# 1-Schematic_ESP32_Wroom_mini.net
KiCad netlist of a schematic drawn in EasyEDA
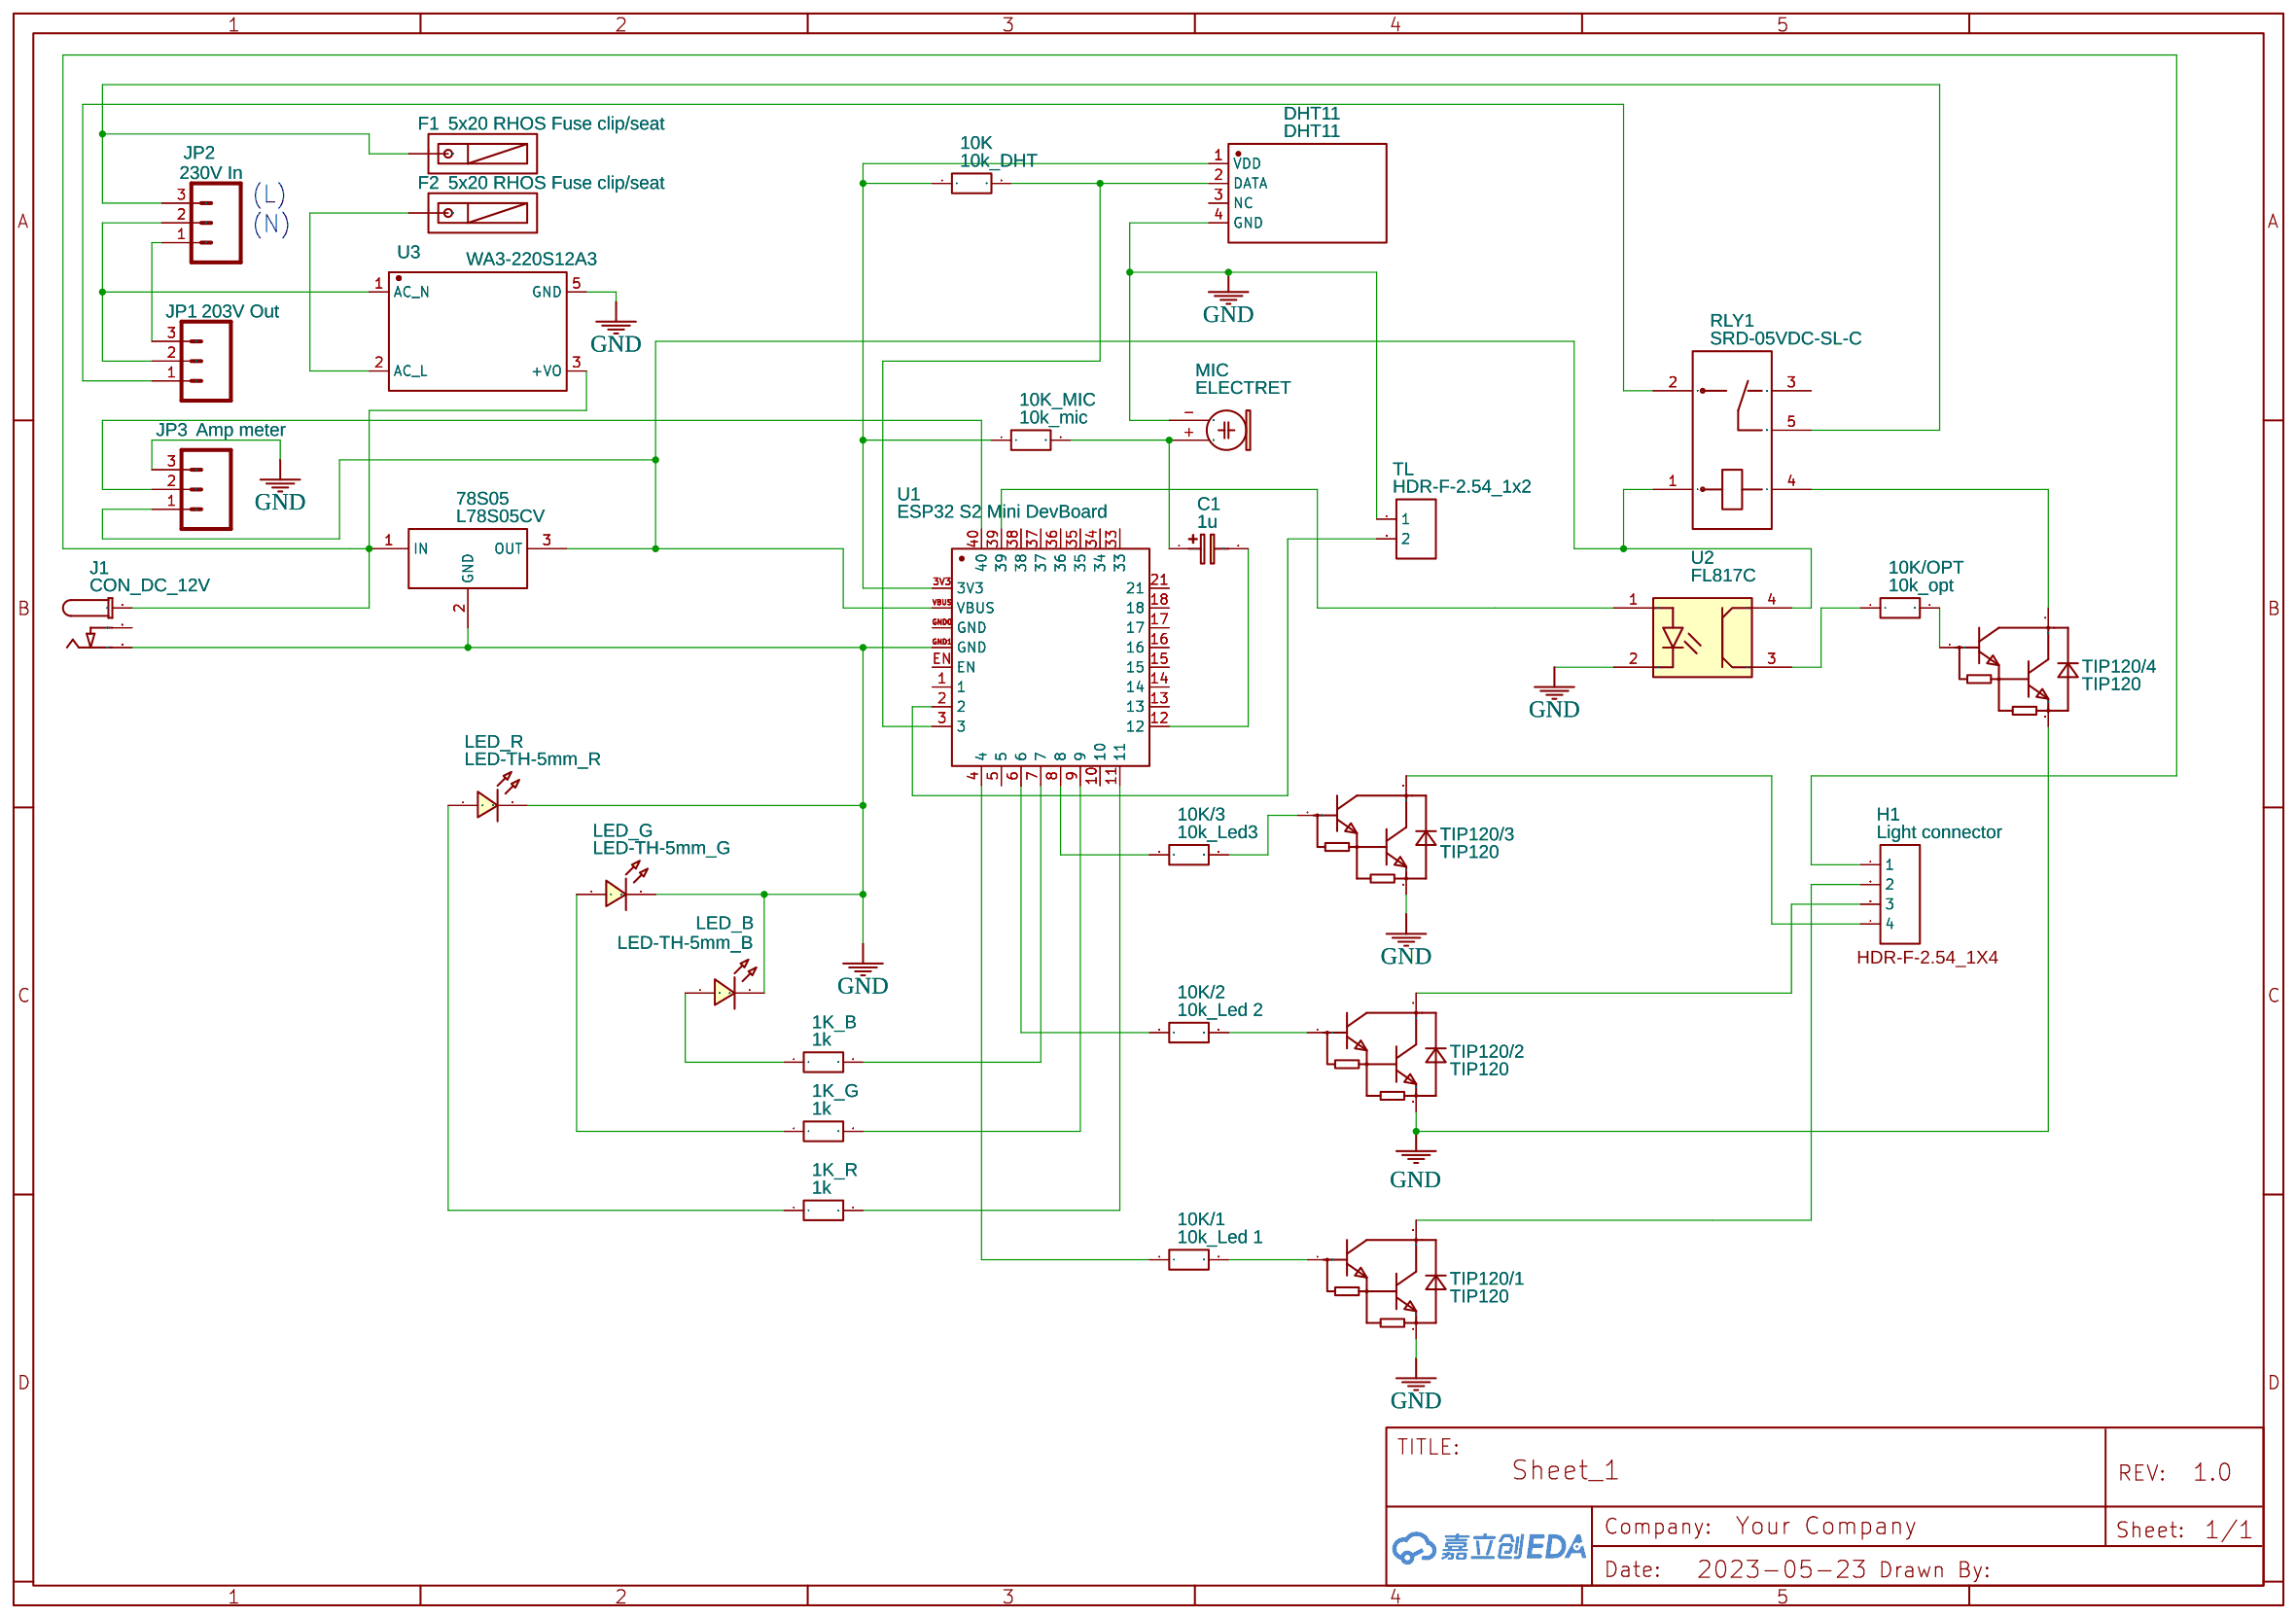
[diagram p0: schematic sheet]

(export (version "E")
  (design (tool "Eeschema 10.0.6"))
  (components
    (comp (ref "1K_B") (value "1k") (libsource (lib "") (part "R_AXIAL-0.3_EU_1")))
    (comp (ref "1K_G") (value "1k") (libsource (lib "") (part "R_AXIAL-0.3_EU")))
    (comp (ref "1K_R") (value "1k") (libsource (lib "") (part "R_AXIAL-0.3_EU_2")))
    (comp (ref "10K") (value "10k_DHT") (libsource (lib "") (part "R_AXIAL-0.4_EU_3")))
    (comp (ref "10K/1") (value "10k_Led 1") (libsource (lib "") (part "R_AXIAL-0.4_EU_2")))
    (comp (ref "10K/2") (value "10k_Led 2") (libsource (lib "") (part "R_AXIAL-0.4_EU_2")))
    (comp (ref "10K/3") (value "10k_Led3") (libsource (lib "") (part "R_AXIAL-0.4_EU_2")))
    (comp (ref "10K/OPT") (value "10k_opt") (libsource (lib "") (part "R_AXIAL-0.4_EU")))
    (comp (ref "10K_MIC") (value "10k_mic") (libsource (lib "") (part "R_AXIAL-0.4_EU_1")))
    (comp (ref "78S05")
      (value "L78S05CV")
      (fields (field (name "Manufacturer") "ST(意法半导体)"))
      (libsource (lib "") (part "L78S05CV"))
    )
    (comp (ref "C1") (value "1u") (libsource (lib "") (part "CE_TH_D3.0×F1.5_EU")))
    (comp (ref "DHT11")
      (value "DHT11")
      (fields (field (name "Manufacturer") "广州奥松"))
      (libsource (lib "") (part "DHT11"))
    )
    (comp (ref "F1")
      (value "5x20 RHOS Fuse clip/seat")
      (fields (field (name "Manufacturer Part") "5x20 环保 保险管夹/座") (field (name "Manufacturer") "xcfuse(旭程)"))
      (libsource (lib "") (part "5x20 RHOS Fuse clip/seat"))
    )
    (comp (ref "F2")
      (value "5x20 RHOS Fuse clip/seat")
      (fields (field (name "Manufacturer Part") "5x20 环保 保险管夹/座") (field (name "Manufacturer") "xcfuse(旭程)"))
      (libsource (lib "") (part "5x20 RHOS Fuse clip/seat"))
    )
    (comp (ref "H1") (value "Light connector") (libsource (lib "") (part "HDR-F-2.54_1x4")))
    (comp (ref "J1") (value "CON_DC_12V") (libsource (lib "") (part "CON_DC_M-DC_PTH")))
    (comp (ref "JP1") (value "203V Out") (libsource (lib "") (part "M03")))
    (comp (ref "JP2") (value "230V In") (libsource (lib "") (part "M03")))
    (comp (ref "JP3") (value "Amp meter") (libsource (lib "") (part "M03")))
    (comp (ref "LED_B") (value "LED-TH-5mm_B") (libsource (lib "") (part "LED-TH-5mm_B")))
    (comp (ref "LED_G")
      (value "LED-TH-5mm_G")
      (fields
        (field (name "Manufacturer Part") "333-2SYGD/S530-E2")
        (field (name "Manufacturer") "EVERLIGHT(台湾亿光)")
      )
      (libsource (lib "") (part "LED-TH-5mm_G"))
    )
    (comp (ref "LED_R")
      (value "LED-TH-5mm_R")
      (fields
        (field (name "Manufacturer Part") "333-2SURD/S530-A3")
        (field (name "Manufacturer") "EVERLIGHT(台湾亿光)")
      )
      (libsource (lib "") (part "LED-TH-5mm_R"))
    )
    (comp (ref "MIC") (value "ELECTRET") (libsource (lib "") (part "ELECTRET")))
    (comp (ref "RLY1")
      (value "SRD-05VDC-SL-C")
      (fields (field (name "Manufacturer") "松乐"))
      (libsource (lib "") (part "SRD-05VDC-SL-C"))
    )
    (comp (ref "TIP120/1")
      (value "TIP120")
      (fields (field (name "Manufacturer") "ST(意法半导体)"))
      (libsource (lib "") (part "TIP120"))
    )
    (comp (ref "TIP120/2")
      (value "TIP120")
      (fields (field (name "Manufacturer") "ST(意法半导体)"))
      (libsource (lib "") (part "TIP120"))
    )
    (comp (ref "TIP120/3")
      (value "TIP120")
      (fields (field (name "Manufacturer") "ST(意法半导体)"))
      (libsource (lib "") (part "TIP120"))
    )
    (comp (ref "TIP120/4")
      (value "TIP120")
      (fields (field (name "Manufacturer") "ST(意法半导体)"))
      (libsource (lib "") (part "TIP120"))
    )
    (comp (ref "TL") (value "HDR-F-2.54_1x2") (libsource (lib "") (part "HDR-F-2.54_1x2")))
    (comp (ref "U1") (value "ESP32 S2 Mini DevBoard") (libsource (lib "") (part "ESP32 S2 Mini DevBoard")))
    (comp (ref "U2")
      (value "FL817C")
      (fields (field (name "Manufacturer") "FANGJING"))
      (libsource (lib "") (part "FL817C"))
    )
    (comp (ref "U3")
      (value "WA3-220S12A3")
      (fields (field (name "Manufacturer") "AIPULNION(爱浦电子)"))
      (libsource (lib "") (part "WA3-220S12A3"))
    )
  )
  (nets
    (net (code "1") (name "GND") (class "Default")
      (node (ref "78S05") (pin "2") (pinfunction "GND_2") (pintype "passive"))
      (node (ref "DHT11") (pin "4") (pinfunction "GND_4") (pintype "unspecified"))
      (node (ref "J1") (pin "P3") (pinfunction "P2_P3") (pintype "unspecified"))
      (node (ref "JP3") (pin "3") (pinfunction "3_3") (pintype "unspecified"))
      (node (ref "LED_B") (pin "2") (pinfunction "2_2") (pintype "unspecified"))
      (node (ref "LED_G") (pin "2") (pinfunction "2_2") (pintype "unspecified"))
      (node (ref "LED_R") (pin "2") (pinfunction "2_2") (pintype "unspecified"))
      (node (ref "MIC") (pin "-") (pinfunction "1_-") (pintype "unspecified"))
      (node (ref "TIP120/1") (pin "3") (pinfunction "E_3") (pintype "input"))
      (node (ref "TIP120/2") (pin "3") (pinfunction "E_3") (pintype "input"))
      (node (ref "TIP120/3") (pin "3") (pinfunction "E_3") (pintype "input"))
      (node (ref "TIP120/4") (pin "3") (pinfunction "E_3") (pintype "input"))
      (node (ref "TL") (pin "1") (pinfunction "1_1") (pintype "input"))
      (node (ref "U1") (pin "GND1") (pinfunction "GND_GND1") (pintype "unspecified"))
      (node (ref "U2") (pin "2") (pinfunction "2_2") (pintype "unspecified"))
      (node (ref "U3") (pin "5") (pinfunction "GND_5") (pintype "unspecified"))
    )
    (net (code "2") (name "Net-(1K_B-Pad1)") (class "Default")
      (node (ref "1K_B") (pin "1") (pinfunction "1_1") (pintype "unspecified"))
      (node (ref "LED_B") (pin "1") (pinfunction "1_1") (pintype "unspecified"))
    )
    (net (code "3") (name "Net-(1K_B-Pad2)") (class "Default")
      (node (ref "1K_B") (pin "2") (pinfunction "2_2") (pintype "unspecified"))
      (node (ref "U1") (pin "7") (pinfunction "7_7") (pintype "unspecified"))
    )
    (net (code "4") (name "Net-(1K_G-Pad1)") (class "Default")
      (node (ref "1K_G") (pin "1") (pinfunction "1_1") (pintype "unspecified"))
      (node (ref "LED_G") (pin "1") (pinfunction "1_1") (pintype "unspecified"))
    )
    (net (code "5") (name "Net-(1K_G-Pad2)") (class "Default")
      (node (ref "1K_G") (pin "2") (pinfunction "2_2") (pintype "unspecified"))
      (node (ref "U1") (pin "9") (pinfunction "9_9") (pintype "unspecified"))
    )
    (net (code "6") (name "Net-(1K_R-Pad1)") (class "Default")
      (node (ref "1K_R") (pin "1") (pinfunction "1_1") (pintype "unspecified"))
      (node (ref "LED_R") (pin "1") (pinfunction "1_1") (pintype "unspecified"))
    )
    (net (code "7") (name "Net-(1K_R-Pad2)") (class "Default")
      (node (ref "1K_R") (pin "2") (pinfunction "2_2") (pintype "unspecified"))
      (node (ref "U1") (pin "11") (pinfunction "11_11") (pintype "unspecified"))
    )
    (net (code "8") (name "Net-(10K/1-Pad1)") (class "Default")
      (node (ref "10K/1") (pin "1") (pinfunction "1_1") (pintype "unspecified"))
      (node (ref "U1") (pin "4") (pinfunction "4_4") (pintype "unspecified"))
    )
    (net (code "9") (name "Net-(10K/2-Pad1)") (class "Default")
      (node (ref "10K/2") (pin "1") (pinfunction "1_1") (pintype "unspecified"))
      (node (ref "U1") (pin "6") (pinfunction "6_6") (pintype "unspecified"))
    )
    (net (code "10") (name "Net-(10K/3-Pad1)") (class "Default")
      (node (ref "10K/3") (pin "1") (pinfunction "1_1") (pintype "unspecified"))
      (node (ref "U1") (pin "8") (pinfunction "8_8") (pintype "unspecified"))
    )
    (net (code "11") (name "Net-(10K/OPT-Pad1)") (class "Default")
      (node (ref "10K/OPT") (pin "1") (pinfunction "1_1") (pintype "unspecified"))
      (node (ref "U2") (pin "3") (pinfunction "3_3") (pintype "unspecified"))
    )
    (net (code "12") (name "Net-(78S05-IN)") (class "Default")
      (node (ref "78S05") (pin "1") (pinfunction "IN_1") (pintype "passive"))
      (node (ref "H1") (pin "1") (pinfunction "1_1") (pintype "unspecified"))
      (node (ref "J1") (pin "P1") (pinfunction "P1_P1") (pintype "unspecified"))
      (node (ref "U3") (pin "3") (pinfunction "+VO_3") (pintype "unspecified"))
    )
    (net (code "13") (name "Net-(78S05-OUT)") (class "Default")
      (node (ref "78S05") (pin "3") (pinfunction "OUT_3") (pintype "passive"))
      (node (ref "JP3") (pin "1") (pinfunction "1_1") (pintype "unspecified"))
      (node (ref "RLY1") (pin "1") (pinfunction "1_1") (pintype "input"))
      (node (ref "U1") (pin "VBUS") (pinfunction "VBUS_VBUS") (pintype "unspecified"))
      (node (ref "U2") (pin "4") (pinfunction "4_4") (pintype "unspecified"))
    )
    (net (code "14") (name "Net-(C1-Pad2)") (class "Default")
      (node (ref "C1") (pin "2") (pinfunction "2_2") (pintype "unspecified"))
      (node (ref "U1") (pin "12") (pinfunction "12_12") (pintype "unspecified"))
    )
    (net (code "15") (name "Net-(DHT11-DATA)") (class "Default")
      (node (ref "10K") (pin "2") (pinfunction "2_2") (pintype "unspecified"))
      (node (ref "DHT11") (pin "2") (pinfunction "DATA_2") (pintype "unspecified"))
      (node (ref "U1") (pin "3") (pinfunction "3_3") (pintype "unspecified"))
    )
    (net (code "16") (name "Net-(DHT11-VDD)") (class "Default")
      (node (ref "10K") (pin "1") (pinfunction "1_1") (pintype "unspecified"))
      (node (ref "10K_MIC") (pin "1") (pinfunction "1_1") (pintype "unspecified"))
      (node (ref "DHT11") (pin "1") (pinfunction "VDD_1") (pintype "unspecified"))
      (node (ref "U1") (pin "3V3") (pinfunction "3V3_3V3") (pintype "unspecified"))
    )
    (net (code "17") (name "Net-(F1-Pad1)") (class "Default")
      (node (ref "F1") (pin "1") (pinfunction "1_1") (pintype "unspecified"))
      (node (ref "JP2") (pin "3") (pinfunction "3_3") (pintype "unspecified"))
      (node (ref "RLY1") (pin "5") (pinfunction "5_5") (pintype "input"))
    )
    (net (code "18") (name "Net-(JP1-Pad1)") (class "Default")
      (node (ref "JP1") (pin "1") (pinfunction "1_1") (pintype "unspecified"))
      (node (ref "RLY1") (pin "2") (pinfunction "2_2") (pintype "input"))
    )
    (net (code "19") (name "Net-(JP1-Pad3)") (class "Default")
      (node (ref "JP1") (pin "3") (pinfunction "3_3") (pintype "unspecified"))
      (node (ref "JP2") (pin "1") (pinfunction "1_1") (pintype "unspecified"))
    )
    (net (code "20") (name "Net-(JP3-Pad2)") (class "Default")
      (node (ref "JP3") (pin "2") (pinfunction "2_2") (pintype "unspecified"))
      (node (ref "U1") (pin "40") (pinfunction "40_40") (pintype "unspecified"))
    )
    (net (code "21") (name "Net-(MIC-2)") (class "Default")
      (node (ref "10K_MIC") (pin "2") (pinfunction "2_2") (pintype "unspecified"))
      (node (ref "C1") (pin "1") (pinfunction "1_1") (pintype "unspecified"))
      (node (ref "MIC") (pin "+") (pinfunction "2_+") (pintype "unspecified"))
    )
    (net (code "22") (name "Net-(TIP120/1-B)") (class "Default")
      (node (ref "10K/1") (pin "2") (pinfunction "2_2") (pintype "unspecified"))
      (node (ref "TIP120/1") (pin "1") (pinfunction "B_1") (pintype "input"))
    )
    (net (code "23") (name "Net-(TIP120/1-C)") (class "Default")
      (node (ref "H1") (pin "2") (pinfunction "2_2") (pintype "unspecified"))
      (node (ref "TIP120/1") (pin "2") (pinfunction "C_2") (pintype "input"))
    )
    (net (code "24") (name "Net-(TIP120/2-B)") (class "Default")
      (node (ref "10K/2") (pin "2") (pinfunction "2_2") (pintype "unspecified"))
      (node (ref "TIP120/2") (pin "1") (pinfunction "B_1") (pintype "input"))
    )
    (net (code "25") (name "Net-(TIP120/2-C)") (class "Default")
      (node (ref "H1") (pin "3") (pinfunction "3_3") (pintype "unspecified"))
      (node (ref "TIP120/2") (pin "2") (pinfunction "C_2") (pintype "input"))
    )
    (net (code "26") (name "Net-(TIP120/3-B)") (class "Default")
      (node (ref "10K/3") (pin "2") (pinfunction "2_2") (pintype "unspecified"))
      (node (ref "TIP120/3") (pin "1") (pinfunction "B_1") (pintype "input"))
    )
    (net (code "27") (name "Net-(TIP120/3-C)") (class "Default")
      (node (ref "H1") (pin "4") (pinfunction "4_4") (pintype "unspecified"))
      (node (ref "TIP120/3") (pin "2") (pinfunction "C_2") (pintype "input"))
    )
    (net (code "28") (name "Net-(TIP120/4-B)") (class "Default")
      (node (ref "10K/OPT") (pin "2") (pinfunction "2_2") (pintype "unspecified"))
      (node (ref "TIP120/4") (pin "1") (pinfunction "B_1") (pintype "input"))
    )
    (net (code "29") (name "Net-(TIP120/4-C)") (class "Default")
      (node (ref "RLY1") (pin "4") (pinfunction "4_4") (pintype "input"))
      (node (ref "TIP120/4") (pin "2") (pinfunction "C_2") (pintype "input"))
    )
    (net (code "30") (name "Net-(TL-Pad2)") (class "Default")
      (node (ref "TL") (pin "2") (pinfunction "2_2") (pintype "input"))
      (node (ref "U1") (pin "2") (pinfunction "2_2") (pintype "unspecified"))
    )
    (net (code "31") (name "Net-(U1-Pad39)") (class "Default")
      (node (ref "U1") (pin "39") (pinfunction "39_39") (pintype "unspecified"))
      (node (ref "U2") (pin "1") (pinfunction "1_1") (pintype "unspecified"))
    )
    (net (code "32") (name "Net-(U3-AC_L)") (class "Default")
      (node (ref "F2") (pin "1") (pinfunction "1_1") (pintype "unspecified"))
      (node (ref "U3") (pin "2") (pinfunction "AC_L_2") (pintype "unspecified"))
    )
    (net (code "33") (name "Net-(U3-AC_N)") (class "Default")
      (node (ref "JP1") (pin "2") (pinfunction "2_2") (pintype "unspecified"))
      (node (ref "JP2") (pin "2") (pinfunction "2_2") (pintype "unspecified"))
      (node (ref "U3") (pin "1") (pinfunction "AC_N_1") (pintype "unspecified"))
    )
    (net (code "34") (name "unconnected-(DHT11-NC-Pad3)") (class "Default")
      (node (ref "DHT11") (pin "3") (pinfunction "NC_3") (pintype "unspecified"))
    )
    (net (code "35") (name "unconnected-(J1-P3-PadP2)") (class "Default")
      (node (ref "J1") (pin "P2") (pinfunction "P3_P2") (pintype "unspecified"))
    )
    (net (code "36") (name "unconnected-(RLY1-Pad3)") (class "Default")
      (node (ref "RLY1") (pin "3") (pinfunction "3_3") (pintype "input"))
    )
    (net (code "37") (name "unconnected-(U1-GND-PadGND0)") (class "Default")
      (node (ref "U1") (pin "GND0") (pinfunction "GND_GND0") (pintype "unspecified"))
    )
    (net (code "38") (name "unconnected-(U1-Pad1)") (class "Default")
      (node (ref "U1") (pin "1") (pinfunction "1_1") (pintype "unspecified"))
    )
    (net (code "39") (name "unconnected-(U1-Pad5)") (class "Default")
      (node (ref "U1") (pin "5") (pinfunction "5_5") (pintype "unspecified"))
    )
    (net (code "40") (name "unconnected-(U1-Pad10)") (class "Default")
      (node (ref "U1") (pin "10") (pinfunction "10_10") (pintype "unspecified"))
    )
    (net (code "41") (name "unconnected-(U1-Pad13)") (class "Default")
      (node (ref "U1") (pin "13") (pinfunction "13_13") (pintype "unspecified"))
    )
    (net (code "42") (name "unconnected-(U1-Pad14)") (class "Default")
      (node (ref "U1") (pin "14") (pinfunction "14_14") (pintype "unspecified"))
    )
    (net (code "43") (name "unconnected-(U1-Pad15)") (class "Default")
      (node (ref "U1") (pin "15") (pinfunction "15_15") (pintype "unspecified"))
    )
    (net (code "44") (name "unconnected-(U1-Pad16)") (class "Default")
      (node (ref "U1") (pin "16") (pinfunction "16_16") (pintype "unspecified"))
    )
    (net (code "45") (name "unconnected-(U1-Pad17)") (class "Default")
      (node (ref "U1") (pin "17") (pinfunction "17_17") (pintype "unspecified"))
    )
    (net (code "46") (name "unconnected-(U1-Pad18)") (class "Default")
      (node (ref "U1") (pin "18") (pinfunction "18_18") (pintype "unspecified"))
    )
    (net (code "47") (name "unconnected-(U1-Pad21)") (class "Default")
      (node (ref "U1") (pin "21") (pinfunction "21_21") (pintype "unspecified"))
    )
    (net (code "48") (name "unconnected-(U1-Pad33)") (class "Default")
      (node (ref "U1") (pin "33") (pinfunction "33_33") (pintype "unspecified"))
    )
    (net (code "49") (name "unconnected-(U1-Pad34)") (class "Default")
      (node (ref "U1") (pin "34") (pinfunction "34_34") (pintype "unspecified"))
    )
    (net (code "50") (name "unconnected-(U1-Pad35)") (class "Default")
      (node (ref "U1") (pin "35") (pinfunction "35_35") (pintype "unspecified"))
    )
    (net (code "51") (name "unconnected-(U1-Pad36)") (class "Default")
      (node (ref "U1") (pin "36") (pinfunction "36_36") (pintype "unspecified"))
    )
    (net (code "52") (name "unconnected-(U1-Pad37)") (class "Default")
      (node (ref "U1") (pin "37") (pinfunction "37_37") (pintype "unspecified"))
    )
    (net (code "53") (name "unconnected-(U1-Pad38)") (class "Default")
      (node (ref "U1") (pin "38") (pinfunction "38_38") (pintype "unspecified"))
    )
    (net (code "54") (name "unconnected-(U1-PadEN)") (class "Default")
      (node (ref "U1") (pin "EN") (pinfunction "EN_EN") (pintype "unspecified"))
    )
  )
)
